# buck.net
KiCad netlist of a schematic drawn in EAGLE
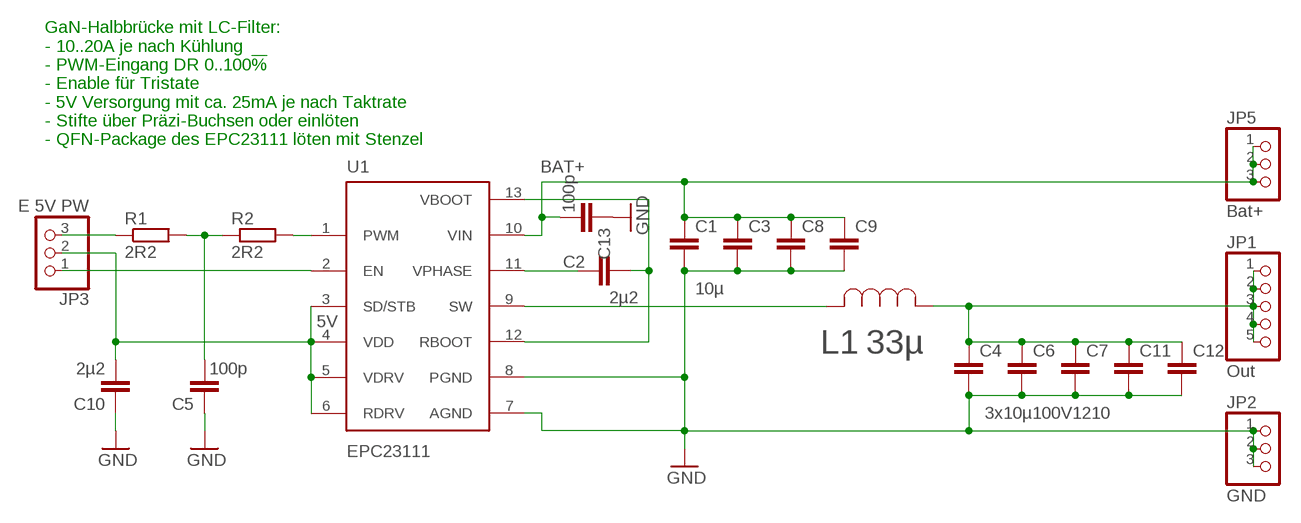
[diagram p0: schematic, sheet 1]

(export (version "E")
  (design (tool "Eeschema 10.0.6"))
  (components
    (comp (ref "C1")
      (value "10µ")
      (footprint "eagle-import:C1210K")
      (libsource (lib "eagle-import") (part "C-EUC1210K"))
    )
    (comp (ref "C2")
      (value "2µ2")
      (footprint "eagle-import:C0603K")
      (libsource (lib "eagle-import") (part "C-EUC0603K"))
    )
    (comp (ref "C3")
      (value "10µ100V1210")
      (footprint "eagle-import:C1210K")
      (libsource (lib "eagle-import") (part "C-EUC1210K"))
    )
    (comp (ref "C4")
      (value "10µ")
      (footprint "eagle-import:C1210K")
      (libsource (lib "eagle-import") (part "C-EUC1210K"))
    )
    (comp (ref "C5")
      (value "100p")
      (footprint "eagle-import:C0603K")
      (libsource (lib "eagle-import") (part "C-EUC0603K"))
    )
    (comp (ref "C6")
      (value "3x10µ100V1210")
      (footprint "eagle-import:C1210K")
      (libsource (lib "eagle-import") (part "C-EUC1210K"))
    )
    (comp (ref "C7")
      (value "10µ100V1210")
      (footprint "eagle-import:C1210K")
      (libsource (lib "eagle-import") (part "C-EUC1210K"))
    )
    (comp (ref "C8")
      (value "10µ100V1210")
      (footprint "eagle-import:C1210K")
      (libsource (lib "eagle-import") (part "C-EUC1210K"))
    )
    (comp (ref "C9")
      (value "10µ100V1210")
      (footprint "eagle-import:C1210K")
      (libsource (lib "eagle-import") (part "C-EUC1210K"))
    )
    (comp (ref "C10")
      (value "2µ2")
      (footprint "eagle-import:C0603K")
      (libsource (lib "eagle-import") (part "C-EUC0603K"))
    )
    (comp (ref "C11")
      (value "10µ100V1210")
      (footprint "eagle-import:C1210K")
      (libsource (lib "eagle-import") (part "C-EUC1210K"))
    )
    (comp (ref "C12")
      (value "10µ100V1210")
      (footprint "eagle-import:C1210K")
      (libsource (lib "eagle-import") (part "C-EUC1210K"))
    )
    (comp (ref "C13")
      (value "100p")
      (footprint "eagle-import:C1206K")
      (libsource (lib "eagle-import") (part "C-EUC1206K"))
    )
    (comp (ref "JP1")
      (value "Out")
      (footprint "eagle-import:1X05")
      (libsource (lib "eagle-import") (part "PINHD-1X5"))
    )
    (comp (ref "JP2")
      (value "GND")
      (footprint "eagle-import:1X03")
      (libsource (lib "eagle-import") (part "PINHD-1X3"))
    )
    (comp (ref "JP3")
      (value "E 5V PW")
      (footprint "eagle-import:1X03")
      (libsource (lib "eagle-import") (part "PINHD-1X3"))
    )
    (comp (ref "JP5")
      (value "Bat+")
      (footprint "eagle-import:1X03")
      (libsource (lib "eagle-import") (part "PINHD-1X3"))
    )
    (comp (ref "L1")
      (value "33µ")
      (footprint "eagle-import:IND_PA4349.333ANLT_PUL-M")
      (fields
        (field (name "MANUFACTURER_PART_NUMBER") "PA4349.333ANLT")
        (field (name "COPYRIGHT") "Copyright (C) 2021 Ultra Librarian. All rights reserved.")
      )
      (libsource (lib "eagle-import") (part "PA4349.333ANLTIND_PA4349.333ANLT_PUL-M"))
    )
    (comp (ref "R1")
      (value "2R2")
      (footprint "eagle-import:R0603")
      (libsource (lib "eagle-import") (part "R-EU_R0603"))
    )
    (comp (ref "R2")
      (value "2R2")
      (footprint "eagle-import:R0603")
      (libsource (lib "eagle-import") (part "R-EU_R0603"))
    )
    (comp (ref "U1")
      (value "EPC23111")
      (footprint "eagle-import:EPC23111_QFN13_EPC_LP")
      (libsource (lib "eagle-import") (part "EPC23111"))
    )
  )
  (nets
    (net (code "1") (name "/5V") (class "Default")
      (node (ref "C10") (pin "2") (pinfunction "2_2") (pintype "passive"))
      (node (ref "JP3") (pin "2") (pinfunction "2_2") (pintype "passive"))
      (node (ref "U1") (pin "3") (pinfunction "SD/STB_3") (pintype "bidirectional"))
      (node (ref "U1") (pin "4") (pinfunction "VDD_4") (pintype "bidirectional"))
      (node (ref "U1") (pin "5") (pinfunction "VDRV_5") (pintype "bidirectional"))
      (node (ref "U1") (pin "6") (pinfunction "RDRV_6") (pintype "bidirectional"))
    )
    (net (code "2") (name "/BAT+") (class "Default")
      (node (ref "C1") (pin "1") (pinfunction "1_1") (pintype "passive"))
      (node (ref "C13") (pin "2") (pinfunction "2_2") (pintype "passive"))
      (node (ref "C3") (pin "1") (pinfunction "1_1") (pintype "passive"))
      (node (ref "C8") (pin "1") (pinfunction "1_1") (pintype "passive"))
      (node (ref "C9") (pin "1") (pinfunction "1_1") (pintype "passive"))
      (node (ref "JP5") (pin "1") (pinfunction "1_1") (pintype "passive"))
      (node (ref "JP5") (pin "2") (pinfunction "2_2") (pintype "passive"))
      (node (ref "JP5") (pin "3") (pinfunction "3_3") (pintype "passive"))
      (node (ref "U1") (pin "10") (pinfunction "VIN_10") (pintype "bidirectional"))
    )
    (net (code "3") (name "GND") (class "Default")
      (node (ref "C1") (pin "2") (pinfunction "2_2") (pintype "passive"))
      (node (ref "C10") (pin "1") (pinfunction "1_1") (pintype "passive"))
      (node (ref "C11") (pin "2") (pinfunction "2_2") (pintype "passive"))
      (node (ref "C12") (pin "2") (pinfunction "2_2") (pintype "passive"))
      (node (ref "C13") (pin "1") (pinfunction "1_1") (pintype "passive"))
      (node (ref "C3") (pin "2") (pinfunction "2_2") (pintype "passive"))
      (node (ref "C4") (pin "2") (pinfunction "2_2") (pintype "passive"))
      (node (ref "C5") (pin "1") (pinfunction "1_1") (pintype "passive"))
      (node (ref "C6") (pin "2") (pinfunction "2_2") (pintype "passive"))
      (node (ref "C7") (pin "2") (pinfunction "2_2") (pintype "passive"))
      (node (ref "C8") (pin "2") (pinfunction "2_2") (pintype "passive"))
      (node (ref "C9") (pin "2") (pinfunction "2_2") (pintype "passive"))
      (node (ref "JP2") (pin "1") (pinfunction "1_1") (pintype "passive"))
      (node (ref "JP2") (pin "2") (pinfunction "2_2") (pintype "passive"))
      (node (ref "JP2") (pin "3") (pinfunction "3_3") (pintype "passive"))
      (node (ref "U1") (pin "7") (pinfunction "AGND_7") (pintype "bidirectional"))
      (node (ref "U1") (pin "8") (pinfunction "PGND_8") (pintype "bidirectional"))
    )
    (net (code "4") (name "Net-(C5-Pad2)") (class "Default")
      (node (ref "C5") (pin "2") (pinfunction "2_2") (pintype "passive"))
      (node (ref "R1") (pin "2") (pinfunction "2_2") (pintype "passive"))
      (node (ref "R2") (pin "1") (pinfunction "1_1") (pintype "passive"))
    )
    (net (code "5") (name "Net-(C11-Pad1)") (class "Default")
      (node (ref "C11") (pin "1") (pinfunction "1_1") (pintype "passive"))
      (node (ref "C12") (pin "1") (pinfunction "1_1") (pintype "passive"))
      (node (ref "C4") (pin "1") (pinfunction "1_1") (pintype "passive"))
      (node (ref "C6") (pin "1") (pinfunction "1_1") (pintype "passive"))
      (node (ref "C7") (pin "1") (pinfunction "1_1") (pintype "passive"))
      (node (ref "JP1") (pin "1") (pinfunction "1_1") (pintype "passive"))
      (node (ref "JP1") (pin "2") (pinfunction "2_2") (pintype "passive"))
      (node (ref "JP1") (pin "3") (pinfunction "3_3") (pintype "passive"))
      (node (ref "JP1") (pin "4") (pinfunction "4_4") (pintype "passive"))
      (node (ref "JP1") (pin "5") (pinfunction "5_5") (pintype "passive"))
      (node (ref "L1") (pin "1") (pinfunction "1_1") (pintype "passive"))
    )
    (net (code "6") (name "Net-(JP3-Pad3)") (class "Default")
      (node (ref "JP3") (pin "3") (pinfunction "3_3") (pintype "passive"))
      (node (ref "R1") (pin "1") (pinfunction "1_1") (pintype "passive"))
    )
    (net (code "7") (name "Net-(U1-EN)") (class "Default")
      (node (ref "JP3") (pin "1") (pinfunction "1_1") (pintype "passive"))
      (node (ref "U1") (pin "2") (pinfunction "EN_2") (pintype "bidirectional"))
    )
    (net (code "8") (name "Net-(U1-PWM)") (class "Default")
      (node (ref "R2") (pin "2") (pinfunction "2_2") (pintype "passive"))
      (node (ref "U1") (pin "1") (pinfunction "PWM_1") (pintype "bidirectional"))
    )
    (net (code "9") (name "Net-(U1-RBOOT)") (class "Default")
      (node (ref "C2") (pin "1") (pinfunction "1_1") (pintype "passive"))
      (node (ref "U1") (pin "12") (pinfunction "RBOOT_12") (pintype "bidirectional"))
      (node (ref "U1") (pin "13") (pinfunction "VBOOT_13") (pintype "bidirectional"))
    )
    (net (code "10") (name "Net-(U1-SW)") (class "Default")
      (node (ref "L1") (pin "2") (pinfunction "2_2") (pintype "passive"))
      (node (ref "U1") (pin "9") (pinfunction "SW_9") (pintype "bidirectional"))
    )
    (net (code "11") (name "Net-(U1-VPHASE)") (class "Default")
      (node (ref "C2") (pin "2") (pinfunction "2_2") (pintype "passive"))
      (node (ref "U1") (pin "11") (pinfunction "VPHASE_11") (pintype "bidirectional"))
    )
  )
)
